# Mod_01.net
KiCad netlist of a schematic drawn in Altium Designer
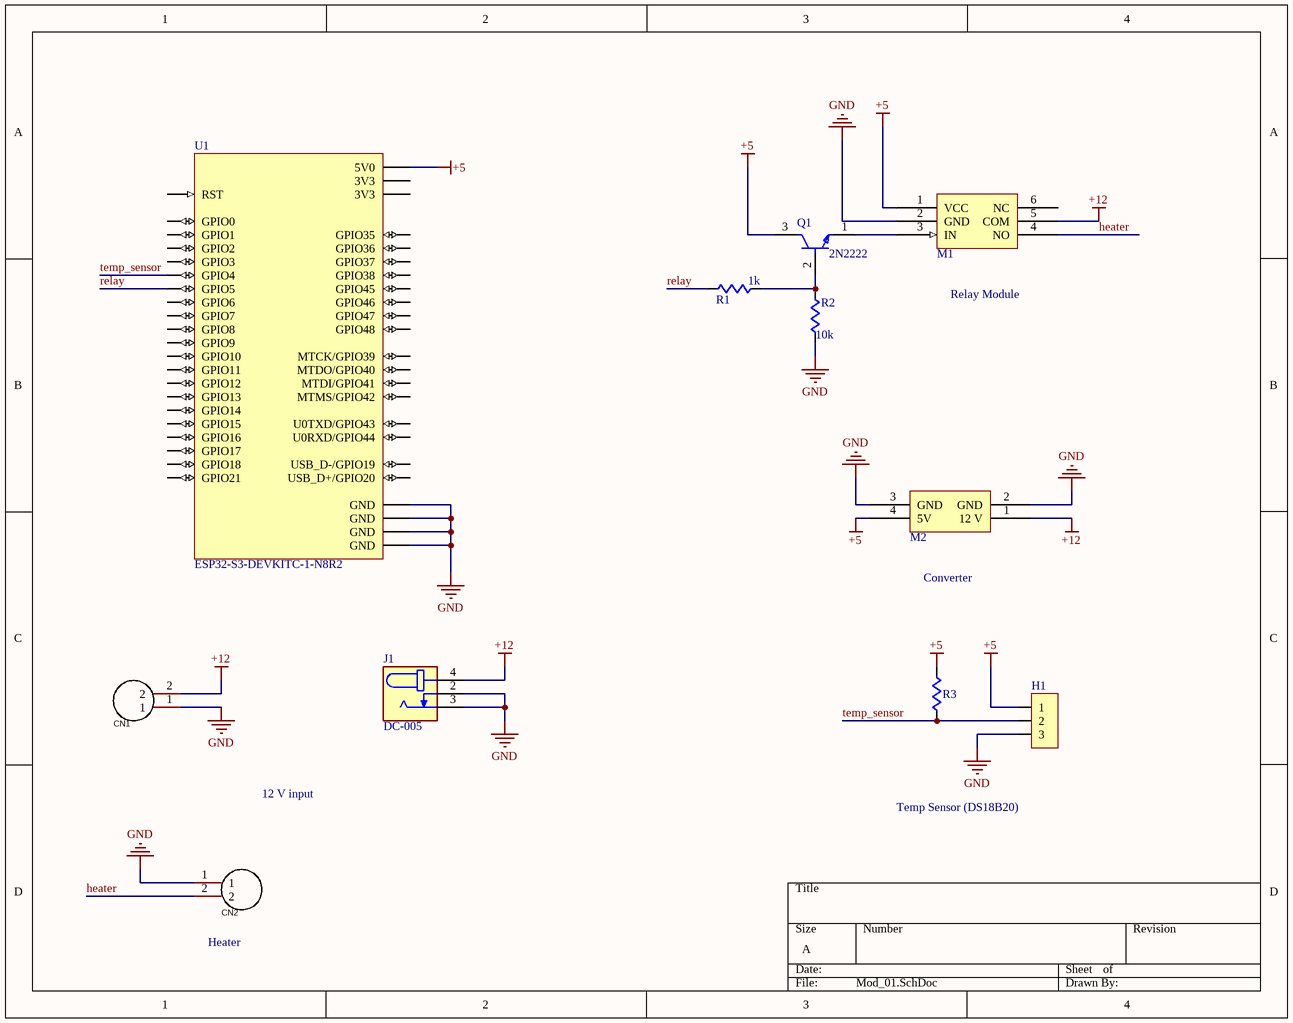
[diagram p0: Mod_01.SchDoc]

(export (version "E")
  (design (tool "Eeschema 10.0.6"))
  (components
    (comp (ref "CN1")
      (value "WJ2EDGRC-5.08-2P")
      (footprint "Terminal Block P5.08-2P")
      (fields (field (name "MANUFACTURER") "KANGNEX(康奈克斯电气)"))
      (libsource (lib "Terminal Block P5.08-2P") (part "WJ2EDGRC-5.08-2P"))
    )
    (comp (ref "CN2")
      (value "WJ2EDGRC-5.08-2P")
      (footprint "Terminal Block P5.08-2P")
      (fields (field (name "MANUFACTURER") "KANGNEX(康奈克斯电气)"))
      (libsource (lib "Terminal Block P5.08-2P") (part "WJ2EDGRC-5.08-2P"))
    )
    (comp (ref "H1")
      (value "Header 1x3")
      (footprint "Header 1x3 male")
      (libsource (lib "Pin Header") (part "Header 1x3"))
    )
    (comp (ref "J1")
      (value "DC-005")
      (footprint "NINIGI_DC-005")
      (description "DC Jack")
      (libsource (lib "DC-005") (part "DC-005"))
    )
    (comp (ref "M1")
      (value "Relay Mod")
      (footprint "Relay Mod1")
      (libsource (lib "Relay Mod") (part "Relay Mod"))
    )
    (comp (ref "M2")
      (value "LM2596")
      (footprint "LM2596 Mod")
      (libsource (lib "LM2596 Mod") (part "LM2596 Mod"))
    )
    (comp (ref "Q1")
      (value "2N2222")
      (footprint "FP-JAN2N2222A-MFG")
      (description "TRANS NPN 50V 0.8A TO218")
      (libsource (lib "2N2222") (part "CMP-06366-000013-1"))
    )
    (comp (ref "R1")
      (value "1k")
      (footprint "RESA60-630X240")
      (description "Axial Resistor,")
      (fields (field (name "TOLERANCE") "1%"))
      (libsource (lib "Resistor Generic") (part "CMP-1659-00075-1"))
    )
    (comp (ref "R2")
      (value "10k")
      (footprint "RESA60-630X240")
      (description "Axial Resistor,")
      (fields (field (name "TOLERANCE") "1%"))
      (libsource (lib "Resistor Generic") (part "CMP-1659-00075-1"))
    )
    (comp (ref "R3")
      (value "4.7k")
      (footprint "RESA60-630X240")
      (description "Axial Resistor,")
      (fields (field (name "TOLERANCE") "1%"))
      (libsource (lib "Resistor Generic") (part "CMP-1659-00075-1_1"))
    )
    (comp (ref "U1")
      (value "ESP32-S3-DEVKITC-1-N8R2")
      (footprint "XCVR_ESP32-S3-DEVKITC-1-N8R2")
      (fields (field (name "MF") "Espressif Systems"))
      (libsource (lib "ESP32-S3-DEVKITC-1-N8R2") (part "ESP32-S3-DEVKITC-1-N8R2"))
    )
  )
  (nets
    (net (code "1") (name "+5") (class "Default")
      (node (ref "H1") (pin "1") (pinfunction "1_1") (pintype "passive"))
      (node (ref "M1") (pin "1") (pinfunction "VCC_1") (pintype "power_in"))
      (node (ref "M2") (pin "4") (pinfunction "5V_4") (pintype "power_in"))
      (node (ref "Q1") (pin "3") (pinfunction "C_3") (pintype "passive"))
      (node (ref "R3") (pin "2") (pinfunction "2_2") (pintype "passive"))
      (node (ref "U1") (pin "J1_21") (pinfunction "5V0_J1_21") (pintype "power_in"))
    )
    (net (code "2") (name "+12") (class "Default")
      (node (ref "CN1") (pin "2") (pinfunction "2_2") (pintype "passive"))
      (node (ref "J1") (pin "4") (pinfunction "2_4") (pintype "passive"))
      (node (ref "M1") (pin "5") (pinfunction "COM_5") (pintype "power_in"))
      (node (ref "M2") (pin "1") (pinfunction "12_V_1") (pintype "power_in"))
    )
    (net (code "3") (name "/heater") (class "Default")
      (node (ref "CN2") (pin "2") (pinfunction "2_2") (pintype "passive"))
      (node (ref "M1") (pin "4") (pinfunction "NO_4") (pintype "power_in"))
    )
    (net (code "4") (name "/relay") (class "Default")
      (node (ref "R1") (pin "1") (pinfunction "1_1") (pintype "passive"))
      (node (ref "U1") (pin "J1_5") (pinfunction "GPIO5_J1_5") (pintype "bidirectional"))
    )
    (net (code "5") (name "/temp_sensor") (class "Default")
      (node (ref "H1") (pin "2") (pinfunction "2_2") (pintype "passive"))
      (node (ref "R3") (pin "1") (pinfunction "1_1") (pintype "passive"))
      (node (ref "U1") (pin "J1_4") (pinfunction "GPIO4_J1_4") (pintype "bidirectional"))
    )
    (net (code "6") (name "GND") (class "Default")
      (node (ref "CN1") (pin "1") (pinfunction "1_1") (pintype "passive"))
      (node (ref "CN2") (pin "1") (pinfunction "1_1") (pintype "passive"))
      (node (ref "H1") (pin "3") (pinfunction "3_3") (pintype "passive"))
      (node (ref "J1") (pin "2") (pinfunction "4_2") (pintype "passive"))
      (node (ref "J1") (pin "3") (pinfunction "5_3") (pintype "passive"))
      (node (ref "M1") (pin "2") (pinfunction "GND_2") (pintype "power_in"))
      (node (ref "M2") (pin "2") (pinfunction "GND_2") (pintype "power_in"))
      (node (ref "M2") (pin "3") (pinfunction "GND_3") (pintype "power_in"))
      (node (ref "R2") (pin "1") (pinfunction "1_1") (pintype "passive"))
      (node (ref "U1") (pin "J1_22") (pinfunction "GND_J1_22") (pintype "power_in"))
      (node (ref "U1") (pin "J3_1") (pinfunction "GND_J3_1") (pintype "power_in"))
      (node (ref "U1") (pin "J3_21") (pinfunction "GND_J3_21") (pintype "power_in"))
      (node (ref "U1") (pin "J3_22") (pinfunction "GND_J3_22") (pintype "power_in"))
    )
    (net (code "7") (name "Net-(M1-IN)") (class "Default")
      (node (ref "M1") (pin "3") (pinfunction "IN_3") (pintype "input"))
      (node (ref "Q1") (pin "1") (pinfunction "E_1") (pintype "passive"))
    )
    (net (code "8") (name "Net-(Q1-B)") (class "Default")
      (node (ref "Q1") (pin "2") (pinfunction "B_2") (pintype "passive"))
      (node (ref "R1") (pin "2") (pinfunction "2_2") (pintype "passive"))
      (node (ref "R2") (pin "2") (pinfunction "2_2") (pintype "passive"))
    )
    (net (code "9") (name "unconnected-(M1-NC-Pad6)") (class "Default")
      (node (ref "M1") (pin "6") (pinfunction "NC_6") (pintype "power_in"))
    )
    (net (code "10") (name "unconnected-(U1-3V3-PadJ1_1)") (class "Default")
      (node (ref "U1") (pin "J1_1") (pinfunction "3V3_J1_1") (pintype "power_in"))
    )
    (net (code "11") (name "unconnected-(U1-3V3-PadJ1_2)") (class "Default")
      (node (ref "U1") (pin "J1_2") (pinfunction "3V3_J1_2") (pintype "power_in"))
    )
    (net (code "12") (name "unconnected-(U1-GPIO0-PadJ3_14)") (class "Default")
      (node (ref "U1") (pin "J3_14") (pinfunction "GPIO0_J3_14") (pintype "bidirectional"))
    )
    (net (code "13") (name "unconnected-(U1-GPIO1-PadJ3_4)") (class "Default")
      (node (ref "U1") (pin "J3_4") (pinfunction "GPIO1_J3_4") (pintype "bidirectional"))
    )
    (net (code "14") (name "unconnected-(U1-GPIO2-PadJ3_5)") (class "Default")
      (node (ref "U1") (pin "J3_5") (pinfunction "GPIO2_J3_5") (pintype "bidirectional"))
    )
    (net (code "15") (name "unconnected-(U1-GPIO3-PadJ1_13)") (class "Default")
      (node (ref "U1") (pin "J1_13") (pinfunction "GPIO3_J1_13") (pintype "bidirectional"))
    )
    (net (code "16") (name "unconnected-(U1-GPIO6-PadJ1_6)") (class "Default")
      (node (ref "U1") (pin "J1_6") (pinfunction "GPIO6_J1_6") (pintype "bidirectional"))
    )
    (net (code "17") (name "unconnected-(U1-GPIO7-PadJ1_7)") (class "Default")
      (node (ref "U1") (pin "J1_7") (pinfunction "GPIO7_J1_7") (pintype "bidirectional"))
    )
    (net (code "18") (name "unconnected-(U1-GPIO8-PadJ1_12)") (class "Default")
      (node (ref "U1") (pin "J1_12") (pinfunction "GPIO8_J1_12") (pintype "bidirectional"))
    )
    (net (code "19") (name "unconnected-(U1-GPIO9-PadJ1_15)") (class "Default")
      (node (ref "U1") (pin "J1_15") (pinfunction "GPIO9_J1_15") (pintype "bidirectional"))
    )
    (net (code "20") (name "unconnected-(U1-GPIO10-PadJ1_16)") (class "Default")
      (node (ref "U1") (pin "J1_16") (pinfunction "GPIO10_J1_16") (pintype "bidirectional"))
    )
    (net (code "21") (name "unconnected-(U1-GPIO11-PadJ1_17)") (class "Default")
      (node (ref "U1") (pin "J1_17") (pinfunction "GPIO11_J1_17") (pintype "bidirectional"))
    )
    (net (code "22") (name "unconnected-(U1-GPIO12-PadJ1_18)") (class "Default")
      (node (ref "U1") (pin "J1_18") (pinfunction "GPIO12_J1_18") (pintype "bidirectional"))
    )
    (net (code "23") (name "unconnected-(U1-GPIO13-PadJ1_19)") (class "Default")
      (node (ref "U1") (pin "J1_19") (pinfunction "GPIO13_J1_19") (pintype "bidirectional"))
    )
    (net (code "24") (name "unconnected-(U1-GPIO14-PadJ1_20)") (class "Default")
      (node (ref "U1") (pin "J1_20") (pinfunction "GPIO14_J1_20") (pintype "bidirectional"))
    )
    (net (code "25") (name "unconnected-(U1-GPIO15-PadJ1_8)") (class "Default")
      (node (ref "U1") (pin "J1_8") (pinfunction "GPIO15_J1_8") (pintype "bidirectional"))
    )
    (net (code "26") (name "unconnected-(U1-GPIO16-PadJ1_9)") (class "Default")
      (node (ref "U1") (pin "J1_9") (pinfunction "GPIO16_J1_9") (pintype "bidirectional"))
    )
    (net (code "27") (name "unconnected-(U1-GPIO17-PadJ1_10)") (class "Default")
      (node (ref "U1") (pin "J1_10") (pinfunction "GPIO17_J1_10") (pintype "bidirectional"))
    )
    (net (code "28") (name "unconnected-(U1-GPIO18-PadJ1_11)") (class "Default")
      (node (ref "U1") (pin "J1_11") (pinfunction "GPIO18_J1_11") (pintype "bidirectional"))
    )
    (net (code "29") (name "unconnected-(U1-GPIO21-PadJ3_18)") (class "Default")
      (node (ref "U1") (pin "J3_18") (pinfunction "GPIO21_J3_18") (pintype "bidirectional"))
    )
    (net (code "30") (name "unconnected-(U1-GPIO35-PadJ3_13)") (class "Default")
      (node (ref "U1") (pin "J3_13") (pinfunction "GPIO35_J3_13") (pintype "bidirectional"))
    )
    (net (code "31") (name "unconnected-(U1-GPIO36-PadJ3_12)") (class "Default")
      (node (ref "U1") (pin "J3_12") (pinfunction "GPIO36_J3_12") (pintype "bidirectional"))
    )
    (net (code "32") (name "unconnected-(U1-GPIO37-PadJ3_11)") (class "Default")
      (node (ref "U1") (pin "J3_11") (pinfunction "GPIO37_J3_11") (pintype "bidirectional"))
    )
    (net (code "33") (name "unconnected-(U1-GPIO38-PadJ3_10)") (class "Default")
      (node (ref "U1") (pin "J3_10") (pinfunction "GPIO38_J3_10") (pintype "bidirectional"))
    )
    (net (code "34") (name "unconnected-(U1-GPIO45-PadJ3_15)") (class "Default")
      (node (ref "U1") (pin "J3_15") (pinfunction "GPIO45_J3_15") (pintype "bidirectional"))
    )
    (net (code "35") (name "unconnected-(U1-GPIO46-PadJ1_14)") (class "Default")
      (node (ref "U1") (pin "J1_14") (pinfunction "GPIO46_J1_14") (pintype "bidirectional"))
    )
    (net (code "36") (name "unconnected-(U1-GPIO47-PadJ3_17)") (class "Default")
      (node (ref "U1") (pin "J3_17") (pinfunction "GPIO47_J3_17") (pintype "bidirectional"))
    )
    (net (code "37") (name "unconnected-(U1-GPIO48-PadJ3_16)") (class "Default")
      (node (ref "U1") (pin "J3_16") (pinfunction "GPIO48_J3_16") (pintype "bidirectional"))
    )
    (net (code "38") (name "unconnected-(U1-MTCK{slash}GPIO39-PadJ3_9)") (class "Default")
      (node (ref "U1") (pin "J3_9") (pinfunction "MTCK/GPIO39_J3_9") (pintype "bidirectional"))
    )
    (net (code "39") (name "unconnected-(U1-MTDI{slash}GPIO41-PadJ3_7)") (class "Default")
      (node (ref "U1") (pin "J3_7") (pinfunction "MTDI/GPIO41_J3_7") (pintype "bidirectional"))
    )
    (net (code "40") (name "unconnected-(U1-MTDO{slash}GPIO40-PadJ3_8)") (class "Default")
      (node (ref "U1") (pin "J3_8") (pinfunction "MTDO/GPIO40_J3_8") (pintype "bidirectional"))
    )
    (net (code "41") (name "unconnected-(U1-MTMS{slash}GPIO42-PadJ3_6)") (class "Default")
      (node (ref "U1") (pin "J3_6") (pinfunction "MTMS/GPIO42_J3_6") (pintype "bidirectional"))
    )
    (net (code "42") (name "unconnected-(U1-RST-PadJ1_3)") (class "Default")
      (node (ref "U1") (pin "J1_3") (pinfunction "RST_J1_3") (pintype "input"))
    )
    (net (code "43") (name "unconnected-(U1-U0RXD{slash}GPIO44-PadJ3_3)") (class "Default")
      (node (ref "U1") (pin "J3_3") (pinfunction "U0RXD/GPIO44_J3_3") (pintype "bidirectional"))
    )
    (net (code "44") (name "unconnected-(U1-U0TXD{slash}GPIO43-PadJ3_2)") (class "Default")
      (node (ref "U1") (pin "J3_2") (pinfunction "U0TXD/GPIO43_J3_2") (pintype "bidirectional"))
    )
    (net (code "45") (name "unconnected-(U1-USB_D+{slash}GPIO20-PadJ3_19)") (class "Default")
      (node (ref "U1") (pin "J3_19") (pinfunction "USB_D+/GPIO20_J3_19") (pintype "bidirectional"))
    )
    (net (code "46") (name "unconnected-(U1-USB_D-{slash}GPIO19-PadJ3_20)") (class "Default")
      (node (ref "U1") (pin "J3_20") (pinfunction "USB_D-/GPIO19_J3_20") (pintype "bidirectional"))
    )
  )
)
